# SCH_esp32s-Camper_2025-03-08.net
KiCad netlist of a schematic drawn in EasyEDA
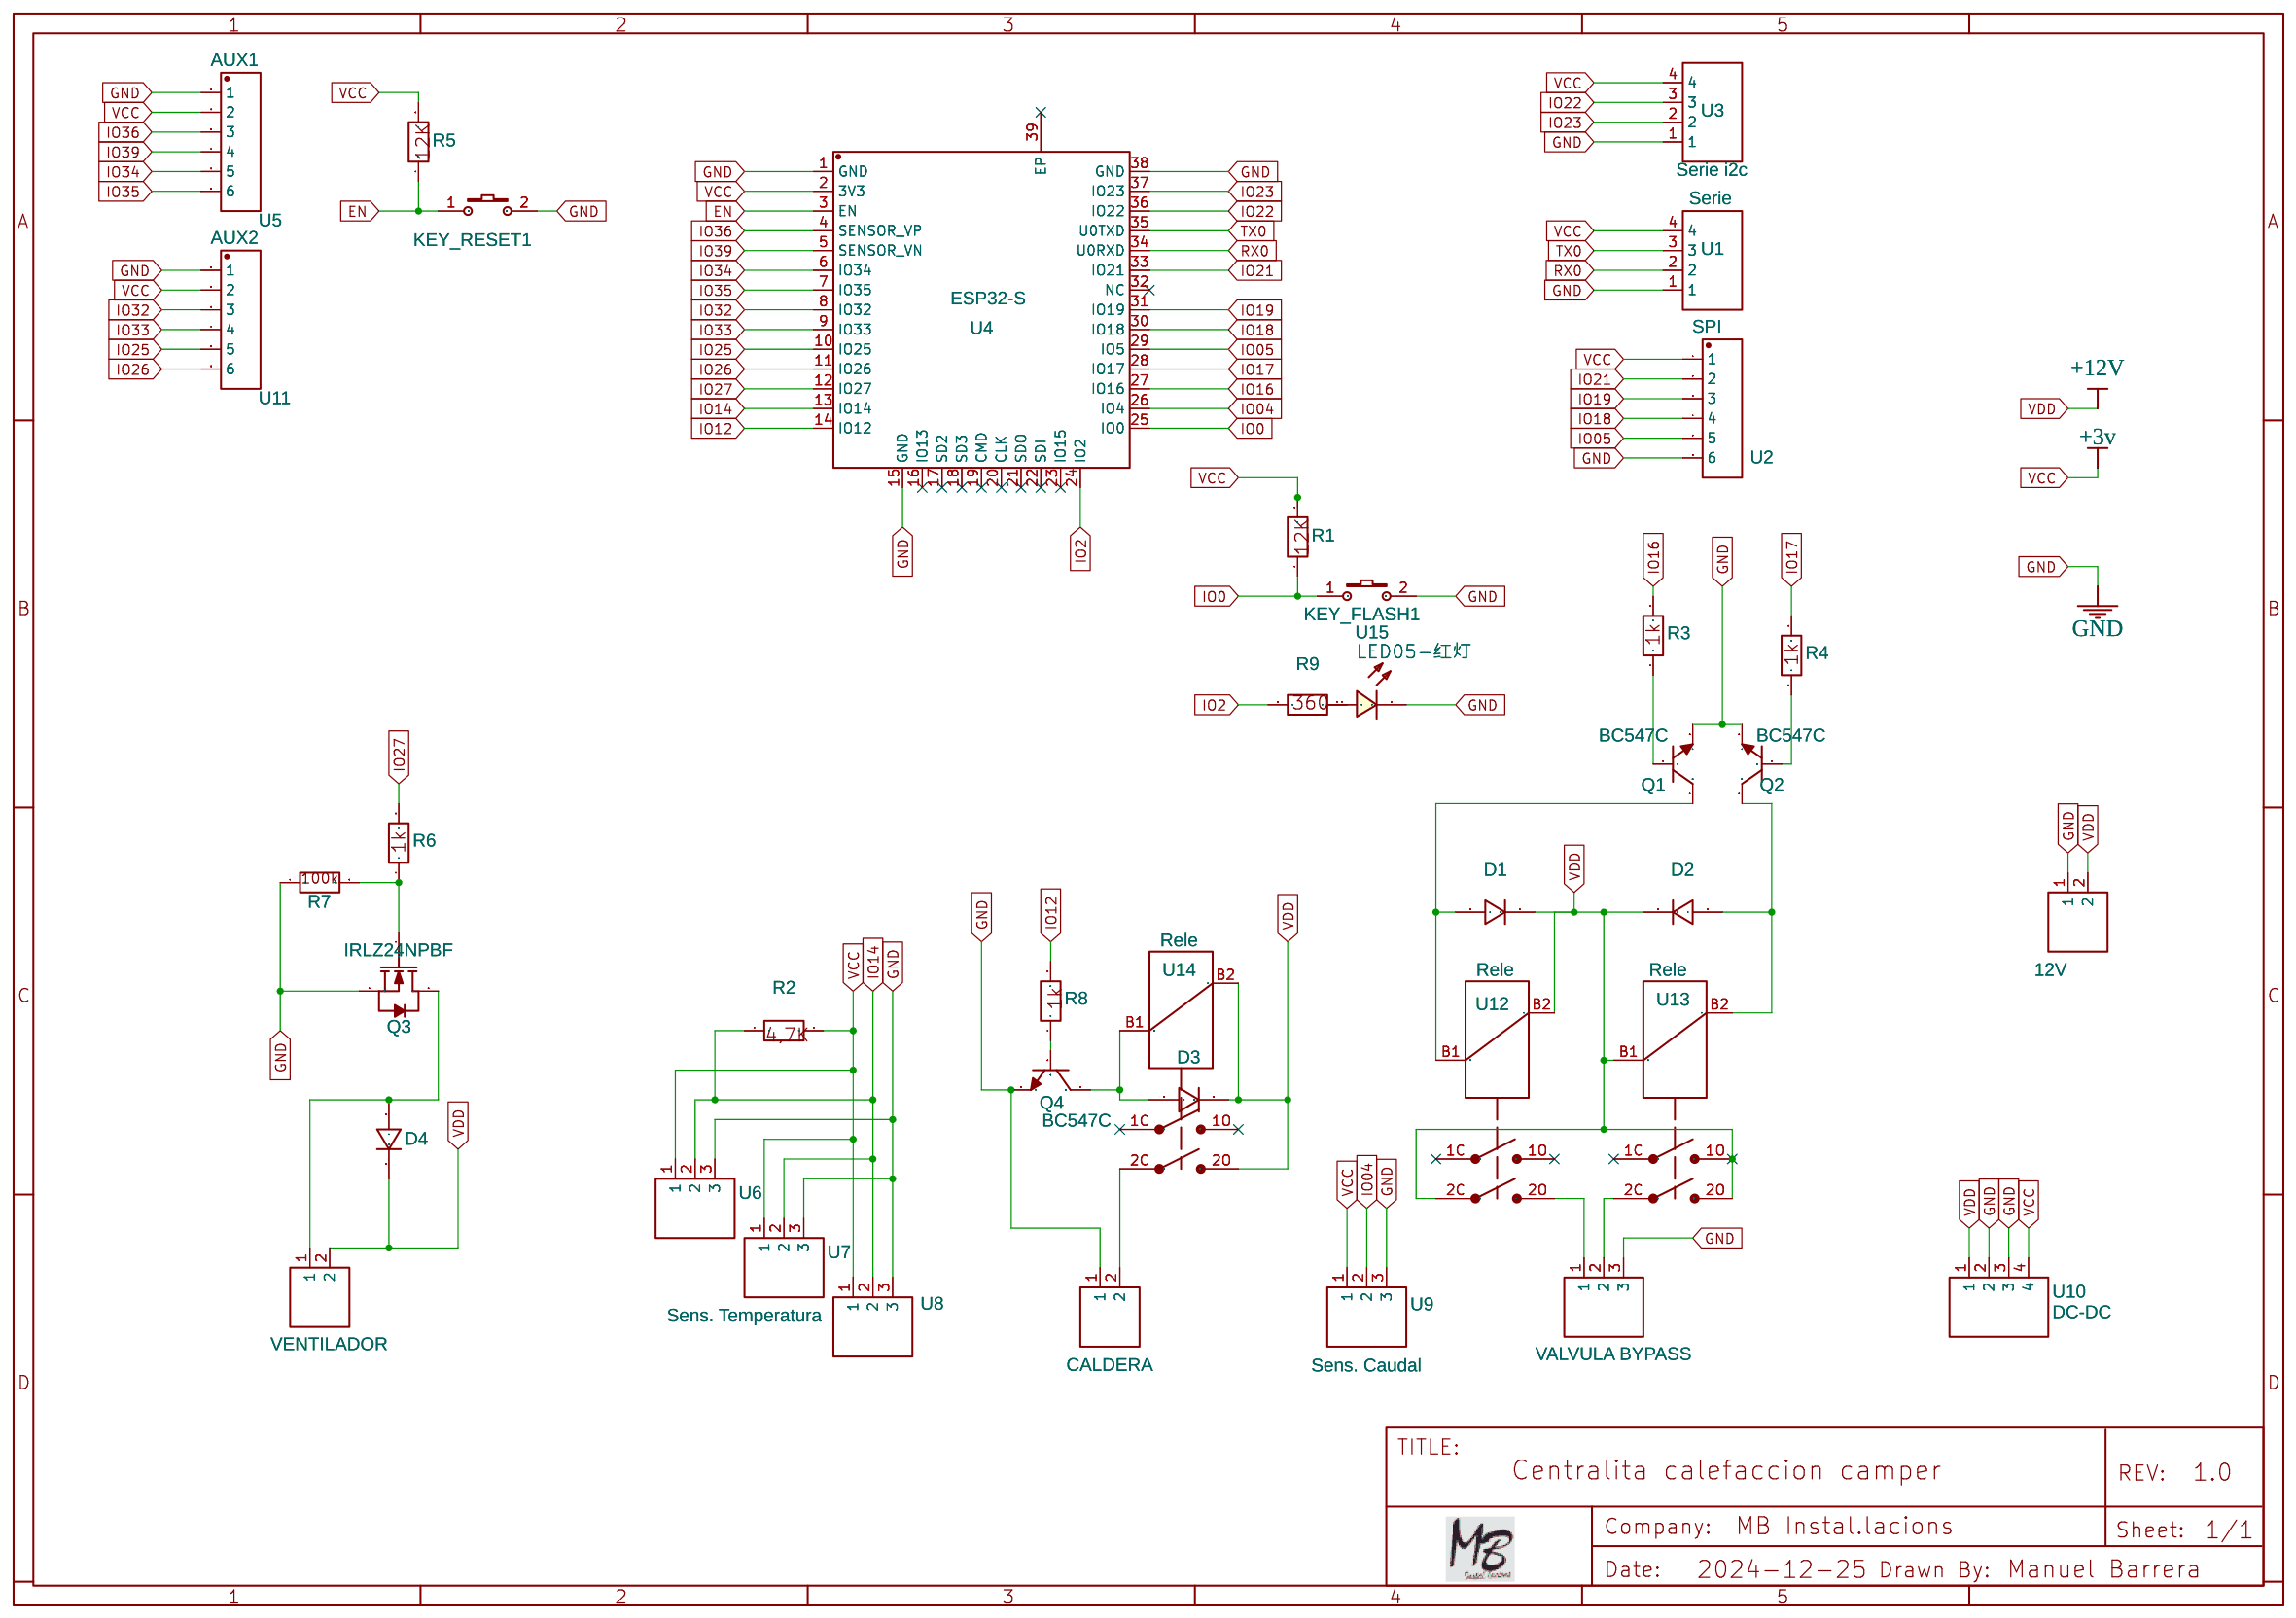
[diagram p0: schematic sheet]

(export (version "E")
  (design (tool "Eeschema 10.0.6"))
  (components
    (comp (ref "CALDERA1")
      (value "CALDERA")
      (fields (field (name "Manufacturer Part") "JST-XH02"))
      (libsource (lib "") (part "JST-XH02_1"))
    )
    (comp (ref "CALDERA2")
      (value "12V")
      (fields (field (name "Manufacturer Part") "JST-XH02"))
      (libsource (lib "") (part "JST-XH02_1"))
    )
    (comp (ref "D1")
      (value "1N4007-C115999")
      (fields (field (name "Manufacturer Part") "1N4007") (field (name "Manufacturer") "PANJIT"))
      (libsource (lib "") (part "1N4007-C115999_1"))
    )
    (comp (ref "D2")
      (value "1N4007-C115999")
      (fields (field (name "Manufacturer Part") "1N4007") (field (name "Manufacturer") "PANJIT"))
      (libsource (lib "") (part "1N4007-C115999"))
    )
    (comp (ref "D3")
      (value "1N4007-C115999")
      (fields (field (name "Manufacturer Part") "1N4007") (field (name "Manufacturer") "PANJIT"))
      (libsource (lib "") (part "1N4007-C115999_1"))
    )
    (comp (ref "D4")
      (value "1N4007-C115999")
      (fields (field (name "Manufacturer Part") "1N4007") (field (name "Manufacturer") "PANJIT"))
      (libsource (lib "") (part "1N4007-C115999_2"))
    )
    (comp (ref "KEY_FLASH1")
      (value "K2-3.6×6.1_SMD")
      (fields (field (name "Manufacturer Part") "K2-1107ST-A4SW-06"))
      (libsource (lib "") (part "K2-3.6×6.1_SMD"))
    )
    (comp (ref "KEY_RESET1")
      (value "K2-3.6×6.1_SMD")
      (fields (field (name "Manufacturer Part") "K2-1107ST-A4SW-06"))
      (libsource (lib "") (part "K2-3.6×6.1_SMD_1"))
    )
    (comp (ref "Q1")
      (value "BC547C")
      (fields (field (name "Manufacturer") "LGE"))
      (libsource (lib "") (part "BC547C_1"))
    )
    (comp (ref "Q2")
      (value "BC547C")
      (fields (field (name "Manufacturer") "LGE"))
      (libsource (lib "") (part "BC547C_2"))
    )
    (comp (ref "Q3")
      (value "IRLZ24NPBF")
      (fields (field (name "Manufacturer") "IR"))
      (libsource (lib "") (part "IRLZ24NPBF"))
    )
    (comp (ref "Q4")
      (value "BC547C")
      (fields (field (name "Manufacturer") "LGE"))
      (libsource (lib "") (part "BC547C"))
    )
    (comp (ref "R1") (value "RESISTENCIA_1/4") (libsource (lib "") (part "RESISTENCIA_1/4_2")))
    (comp (ref "R2") (value "RESISTENCIA_1/4") (libsource (lib "") (part "RESISTENCIA_1/4")))
    (comp (ref "R3") (value "RESISTENCIA_1/4") (libsource (lib "") (part "RESISTENCIA_1/4_1")))
    (comp (ref "R4") (value "RESISTENCIA_1/4") (libsource (lib "") (part "RESISTENCIA_1/4_1")))
    (comp (ref "R5") (value "RESISTENCIA_1/4") (libsource (lib "") (part "RESISTENCIA_1/4_2")))
    (comp (ref "R6") (value "RESISTENCIA_1/4") (libsource (lib "") (part "RESISTENCIA_1/4_1")))
    (comp (ref "R7") (value "RESISTENCIA_1/4") (libsource (lib "") (part "RESISTENCIA_1/4_5")))
    (comp (ref "R8") (value "RESISTENCIA_1/4") (libsource (lib "") (part "RESISTENCIA_1/4_4")))
    (comp (ref "R9") (value "RESISTENCIA_1/4") (libsource (lib "") (part "RESISTENCIA_1/4_3")))
    (comp (ref "U1")
      (value "Serie")
      (fields (field (name "Manufacturer Part") "JST-XH04"))
      (libsource (lib "") (part "JST-XH04"))
    )
    (comp (ref "U2")
      (value "SPI")
      (fields (field (name "Manufacturer Part") "06JQ-BT") (field (name "Manufacturer") "JST"))
      (libsource (lib "") (part "06JQ-BT COPY"))
    )
    (comp (ref "U3")
      (value "Serie i2c")
      (fields (field (name "Manufacturer Part") "JST-XH04"))
      (libsource (lib "") (part "JST-XH04"))
    )
    (comp (ref "U4")
      (value "ESP32-S")
      (fields (field (name "Manufacturer") "Ai-Thinker(安信可)"))
      (libsource (lib "") (part "ESP32-S"))
    )
    (comp (ref "U5")
      (value "AUX1")
      (fields (field (name "Manufacturer Part") "06JQ-BT") (field (name "Manufacturer") "JST"))
      (libsource (lib "") (part "06JQ-BT COPY"))
    )
    (comp (ref "U6")
      (value "Sens. Temperatura")
      (fields (field (name "Manufacturer Part") "JST-XH03"))
      (libsource (lib "") (part "JST-XH03_1"))
    )
    (comp (ref "U7")
      (value "Sens. Temperatura")
      (fields (field (name "Manufacturer Part") "JST-XH03"))
      (libsource (lib "") (part "JST-XH03_1"))
    )
    (comp (ref "U8")
      (value "Sens. Temperatura")
      (fields (field (name "Manufacturer Part") "JST-XH03"))
      (libsource (lib "") (part "JST-XH03_1"))
    )
    (comp (ref "U9")
      (value "Sens. Caudal")
      (fields (field (name "Manufacturer Part") "JST-XH03"))
      (libsource (lib "") (part "JST-XH03_1"))
    )
    (comp (ref "U10")
      (value "DC-DC")
      (fields (field (name "Manufacturer Part") "JST-XH04"))
      (libsource (lib "") (part "JST-XH04_1"))
    )
    (comp (ref "U11")
      (value "AUX2")
      (fields (field (name "Manufacturer Part") "06JQ-BT") (field (name "Manufacturer") "JST"))
      (libsource (lib "") (part "06JQ-BT COPY"))
    )
    (comp (ref "U12") (value "Rele") (libsource (lib "") (part "Relé_REED-RALUX-12V-2C")))
    (comp (ref "U13") (value "Rele") (libsource (lib "") (part "Relé_REED-RALUX-12V-2C")))
    (comp (ref "U14") (value "Rele") (libsource (lib "") (part "Relé_REED-RALUX-12V-2C")))
    (comp (ref "U15") (value "LED05-红灯") (libsource (lib "") (part "LED05-红灯")))
    (comp (ref "VALVULA1")
      (value "VALVULA BYPASS")
      (fields (field (name "Manufacturer Part") "JST-XH03"))
      (libsource (lib "") (part "JST-XH03"))
    )
    (comp (ref "VENTILADOR")
      (value "u9")
      (fields (field (name "Manufacturer Part") "JST-XH02"))
      (libsource (lib "") (part "JST-XH02"))
    )
  )
  (nets
    (net (code "1") (name "EN") (class "Default")
      (node (ref "KEY_RESET1") (pin "1") (pinfunction "1_1") (pintype "unspecified"))
      (node (ref "R5") (pin "1") (pinfunction "1_1") (pintype "unspecified"))
      (node (ref "U4") (pin "3") (pinfunction "EN_3") (pintype "unspecified"))
    )
    (net (code "2") (name "GND") (class "Default")
      (node (ref "CALDERA1") (pin "1") (pinfunction "1_1") (pintype "unspecified"))
      (node (ref "CALDERA2") (pin "1") (pinfunction "1_1") (pintype "unspecified"))
      (node (ref "KEY_FLASH1") (pin "2") (pinfunction "2_2") (pintype "unspecified"))
      (node (ref "KEY_RESET1") (pin "2") (pinfunction "2_2") (pintype "unspecified"))
      (node (ref "Q1") (pin "3") (pinfunction "E_3") (pintype "input"))
      (node (ref "Q2") (pin "3") (pinfunction "E_3") (pintype "input"))
      (node (ref "Q3") (pin "3") (pinfunction "S_3") (pintype "unspecified"))
      (node (ref "Q4") (pin "3") (pinfunction "E_3") (pintype "input"))
      (node (ref "R7") (pin "1") (pinfunction "1_1") (pintype "unspecified"))
      (node (ref "U1") (pin "1") (pinfunction "1_1") (pintype "unspecified"))
      (node (ref "U10") (pin "2") (pinfunction "2_2") (pintype "unspecified"))
      (node (ref "U10") (pin "3") (pinfunction "3_3") (pintype "unspecified"))
      (node (ref "U11") (pin "1") (pinfunction "1_1") (pintype "unspecified"))
      (node (ref "U15") (pin "2") (pinfunction "2_2") (pintype "unspecified"))
      (node (ref "U2") (pin "6") (pinfunction "6_6") (pintype "unspecified"))
      (node (ref "U3") (pin "1") (pinfunction "1_1") (pintype "unspecified"))
      (node (ref "U4") (pin "1") (pinfunction "GND_1") (pintype "unspecified"))
      (node (ref "U4") (pin "15") (pinfunction "GND_15") (pintype "unspecified"))
      (node (ref "U4") (pin "38") (pinfunction "GND_38") (pintype "unspecified"))
      (node (ref "U5") (pin "1") (pinfunction "1_1") (pintype "unspecified"))
      (node (ref "U6") (pin "3") (pinfunction "3_3") (pintype "unspecified"))
      (node (ref "U7") (pin "3") (pinfunction "3_3") (pintype "unspecified"))
      (node (ref "U8") (pin "3") (pinfunction "3_3") (pintype "unspecified"))
      (node (ref "U9") (pin "3") (pinfunction "3_3") (pintype "unspecified"))
      (node (ref "VALVULA1") (pin "3") (pinfunction "3_3") (pintype "unspecified"))
    )
    (net (code "3") (name "IO0") (class "Default")
      (node (ref "KEY_FLASH1") (pin "1") (pinfunction "1_1") (pintype "unspecified"))
      (node (ref "R1") (pin "1") (pinfunction "1_1") (pintype "unspecified"))
      (node (ref "U4") (pin "25") (pinfunction "IO0_25") (pintype "unspecified"))
    )
    (net (code "4") (name "IO2") (class "Default")
      (node (ref "R9") (pin "2") (pinfunction "2_2") (pintype "unspecified"))
      (node (ref "U4") (pin "24") (pinfunction "IO2_24") (pintype "unspecified"))
    )
    (net (code "5") (name "IO04") (class "Default")
      (node (ref "U4") (pin "26") (pinfunction "IO4_26") (pintype "unspecified"))
      (node (ref "U9") (pin "2") (pinfunction "2_2") (pintype "unspecified"))
    )
    (net (code "6") (name "IO05") (class "Default")
      (node (ref "U2") (pin "5") (pinfunction "5_5") (pintype "unspecified"))
      (node (ref "U4") (pin "29") (pinfunction "IO5_29") (pintype "unspecified"))
    )
    (net (code "7") (name "IO12") (class "Default")
      (node (ref "R8") (pin "2") (pinfunction "2_2") (pintype "unspecified"))
      (node (ref "U4") (pin "14") (pinfunction "IO12_14") (pintype "unspecified"))
    )
    (net (code "8") (name "IO14") (class "Default")
      (node (ref "R2") (pin "1") (pinfunction "1_1") (pintype "unspecified"))
      (node (ref "U4") (pin "13") (pinfunction "IO14_13") (pintype "unspecified"))
      (node (ref "U6") (pin "2") (pinfunction "2_2") (pintype "unspecified"))
      (node (ref "U7") (pin "2") (pinfunction "2_2") (pintype "unspecified"))
      (node (ref "U8") (pin "2") (pinfunction "2_2") (pintype "unspecified"))
    )
    (net (code "9") (name "IO16") (class "Default")
      (node (ref "R3") (pin "2") (pinfunction "2_2") (pintype "unspecified"))
      (node (ref "U4") (pin "27") (pinfunction "IO16_27") (pintype "unspecified"))
    )
    (net (code "10") (name "IO17") (class "Default")
      (node (ref "R4") (pin "2") (pinfunction "2_2") (pintype "unspecified"))
      (node (ref "U4") (pin "28") (pinfunction "IO17_28") (pintype "unspecified"))
    )
    (net (code "11") (name "IO18") (class "Default")
      (node (ref "U2") (pin "4") (pinfunction "4_4") (pintype "unspecified"))
      (node (ref "U4") (pin "30") (pinfunction "IO18_30") (pintype "unspecified"))
    )
    (net (code "12") (name "IO19") (class "Default")
      (node (ref "U2") (pin "3") (pinfunction "3_3") (pintype "unspecified"))
      (node (ref "U4") (pin "31") (pinfunction "IO19_31") (pintype "unspecified"))
    )
    (net (code "13") (name "IO21") (class "Default")
      (node (ref "U2") (pin "2") (pinfunction "2_2") (pintype "unspecified"))
      (node (ref "U4") (pin "33") (pinfunction "IO21_33") (pintype "unspecified"))
    )
    (net (code "14") (name "IO22") (class "Default")
      (node (ref "U3") (pin "3") (pinfunction "3_3") (pintype "unspecified"))
      (node (ref "U4") (pin "36") (pinfunction "IO22_36") (pintype "unspecified"))
    )
    (net (code "15") (name "IO23") (class "Default")
      (node (ref "U3") (pin "2") (pinfunction "2_2") (pintype "unspecified"))
      (node (ref "U4") (pin "37") (pinfunction "IO23_37") (pintype "unspecified"))
    )
    (net (code "16") (name "IO25") (class "Default")
      (node (ref "U11") (pin "5") (pinfunction "5_5") (pintype "unspecified"))
      (node (ref "U4") (pin "10") (pinfunction "IO25_10") (pintype "unspecified"))
    )
    (net (code "17") (name "IO26") (class "Default")
      (node (ref "U11") (pin "6") (pinfunction "6_6") (pintype "unspecified"))
      (node (ref "U4") (pin "11") (pinfunction "IO26_11") (pintype "unspecified"))
    )
    (net (code "18") (name "IO27") (class "Default")
      (node (ref "R6") (pin "2") (pinfunction "2_2") (pintype "unspecified"))
      (node (ref "U4") (pin "12") (pinfunction "IO27_12") (pintype "unspecified"))
    )
    (net (code "19") (name "IO32") (class "Default")
      (node (ref "U11") (pin "3") (pinfunction "3_3") (pintype "unspecified"))
      (node (ref "U4") (pin "8") (pinfunction "IO32_8") (pintype "unspecified"))
    )
    (net (code "20") (name "IO33") (class "Default")
      (node (ref "U11") (pin "4") (pinfunction "4_4") (pintype "unspecified"))
      (node (ref "U4") (pin "9") (pinfunction "IO33_9") (pintype "unspecified"))
    )
    (net (code "21") (name "IO34") (class "Default")
      (node (ref "U4") (pin "6") (pinfunction "IO34_6") (pintype "unspecified"))
      (node (ref "U5") (pin "5") (pinfunction "5_5") (pintype "unspecified"))
    )
    (net (code "22") (name "IO35") (class "Default")
      (node (ref "U4") (pin "7") (pinfunction "IO35_7") (pintype "unspecified"))
      (node (ref "U5") (pin "6") (pinfunction "6_6") (pintype "unspecified"))
    )
    (net (code "23") (name "IO36") (class "Default")
      (node (ref "U4") (pin "4") (pinfunction "SENSOR_VP_4") (pintype "unspecified"))
      (node (ref "U5") (pin "3") (pinfunction "3_3") (pintype "unspecified"))
    )
    (net (code "24") (name "IO39") (class "Default")
      (node (ref "U4") (pin "5") (pinfunction "SENSOR_VN_5") (pintype "unspecified"))
      (node (ref "U5") (pin "4") (pinfunction "4_4") (pintype "unspecified"))
    )
    (net (code "25") (name "Net-(CALDERA1-Pad2)") (class "Default")
      (node (ref "CALDERA1") (pin "2") (pinfunction "2_2") (pintype "unspecified"))
      (node (ref "U14") (pin "2C") (pinfunction "1_2C") (pintype "unspecified"))
    )
    (net (code "26") (name "Net-(D1-A)") (class "Default")
      (node (ref "D1") (pin "2") (pinfunction "A_2") (pintype "unspecified"))
      (node (ref "Q1") (pin "1") (pinfunction "C_1") (pintype "input"))
      (node (ref "U12") (pin "B1") (pinfunction "5_B1") (pintype "unspecified"))
    )
    (net (code "27") (name "Net-(D2-A)") (class "Default")
      (node (ref "D2") (pin "2") (pinfunction "A_2") (pintype "unspecified"))
      (node (ref "Q2") (pin "1") (pinfunction "C_1") (pintype "input"))
      (node (ref "U13") (pin "B2") (pinfunction "4_B2") (pintype "unspecified"))
    )
    (net (code "28") (name "Net-(D3-A)") (class "Default")
      (node (ref "D3") (pin "2") (pinfunction "A_2") (pintype "unspecified"))
      (node (ref "Q4") (pin "1") (pinfunction "C_1") (pintype "input"))
      (node (ref "U14") (pin "B1") (pinfunction "5_B1") (pintype "unspecified"))
    )
    (net (code "29") (name "Net-(D4-A)") (class "Default")
      (node (ref "D4") (pin "2") (pinfunction "A_2") (pintype "unspecified"))
      (node (ref "Q3") (pin "2") (pinfunction "D_2") (pintype "unspecified"))
      (node (ref "VENTILADOR") (pin "1") (pinfunction "1_1") (pintype "unspecified"))
    )
    (net (code "30") (name "Net-(Q1-B)") (class "Default")
      (node (ref "Q1") (pin "2") (pinfunction "B_2") (pintype "input"))
      (node (ref "R3") (pin "1") (pinfunction "1_1") (pintype "unspecified"))
    )
    (net (code "31") (name "Net-(Q2-B)") (class "Default")
      (node (ref "Q2") (pin "2") (pinfunction "B_2") (pintype "input"))
      (node (ref "R4") (pin "1") (pinfunction "1_1") (pintype "unspecified"))
    )
    (net (code "32") (name "Net-(Q3-G)") (class "Default")
      (node (ref "Q3") (pin "1") (pinfunction "G_1") (pintype "unspecified"))
      (node (ref "R6") (pin "1") (pinfunction "1_1") (pintype "unspecified"))
      (node (ref "R7") (pin "2") (pinfunction "2_2") (pintype "unspecified"))
    )
    (net (code "33") (name "Net-(Q4-B)") (class "Default")
      (node (ref "Q4") (pin "2") (pinfunction "B_2") (pintype "input"))
      (node (ref "R8") (pin "1") (pinfunction "1_1") (pintype "unspecified"))
    )
    (net (code "34") (name "Net-(R9-Pad1)") (class "Default")
      (node (ref "R9") (pin "1") (pinfunction "1_1") (pintype "unspecified"))
      (node (ref "U15") (pin "1") (pinfunction "1_1") (pintype "unspecified"))
    )
    (net (code "35") (name "Net-(U12-2-Pad2O)") (class "Default")
      (node (ref "U12") (pin "2O") (pinfunction "2_2O") (pintype "unspecified"))
      (node (ref "VALVULA1") (pin "1") (pinfunction "1_1") (pintype "unspecified"))
    )
    (net (code "36") (name "Net-(U13-1-Pad2C)") (class "Default")
      (node (ref "U13") (pin "2C") (pinfunction "1_2C") (pintype "unspecified"))
      (node (ref "VALVULA1") (pin "2") (pinfunction "2_2") (pintype "unspecified"))
    )
    (net (code "37") (name "RX0") (class "Default")
      (node (ref "U1") (pin "2") (pinfunction "2_2") (pintype "unspecified"))
      (node (ref "U4") (pin "34") (pinfunction "U0RXD_34") (pintype "unspecified"))
    )
    (net (code "38") (name "TX0") (class "Default")
      (node (ref "U1") (pin "3") (pinfunction "3_3") (pintype "unspecified"))
      (node (ref "U4") (pin "35") (pinfunction "U0TXD_35") (pintype "unspecified"))
    )
    (net (code "39") (name "VCC") (class "Default")
      (node (ref "R1") (pin "2") (pinfunction "2_2") (pintype "unspecified"))
      (node (ref "R2") (pin "2") (pinfunction "2_2") (pintype "unspecified"))
      (node (ref "R5") (pin "2") (pinfunction "2_2") (pintype "unspecified"))
      (node (ref "U1") (pin "4") (pinfunction "4_4") (pintype "unspecified"))
      (node (ref "U10") (pin "4") (pinfunction "4_4") (pintype "unspecified"))
      (node (ref "U11") (pin "2") (pinfunction "2_2") (pintype "unspecified"))
      (node (ref "U2") (pin "1") (pinfunction "1_1") (pintype "unspecified"))
      (node (ref "U3") (pin "4") (pinfunction "4_4") (pintype "unspecified"))
      (node (ref "U4") (pin "2") (pinfunction "3V3_2") (pintype "unspecified"))
      (node (ref "U5") (pin "2") (pinfunction "2_2") (pintype "unspecified"))
      (node (ref "U6") (pin "1") (pinfunction "1_1") (pintype "unspecified"))
      (node (ref "U7") (pin "1") (pinfunction "1_1") (pintype "unspecified"))
      (node (ref "U8") (pin "1") (pinfunction "1_1") (pintype "unspecified"))
      (node (ref "U9") (pin "1") (pinfunction "1_1") (pintype "unspecified"))
    )
    (net (code "40") (name "VDD") (class "Default")
      (node (ref "CALDERA2") (pin "2") (pinfunction "2_2") (pintype "unspecified"))
      (node (ref "D1") (pin "1") (pinfunction "C_1") (pintype "unspecified"))
      (node (ref "D2") (pin "1") (pinfunction "C_1") (pintype "unspecified"))
      (node (ref "D3") (pin "1") (pinfunction "C_1") (pintype "unspecified"))
      (node (ref "D4") (pin "1") (pinfunction "C_1") (pintype "unspecified"))
      (node (ref "U10") (pin "1") (pinfunction "1_1") (pintype "unspecified"))
      (node (ref "U12") (pin "2C") (pinfunction "1_2C") (pintype "unspecified"))
      (node (ref "U12") (pin "B2") (pinfunction "4_B2") (pintype "unspecified"))
      (node (ref "U13") (pin "1O") (pinfunction "2_1O") (pintype "unspecified"))
      (node (ref "U13") (pin "2O") (pinfunction "2_2O") (pintype "unspecified"))
      (node (ref "U13") (pin "B1") (pinfunction "5_B1") (pintype "unspecified"))
      (node (ref "U14") (pin "2O") (pinfunction "2_2O") (pintype "unspecified"))
      (node (ref "U14") (pin "B2") (pinfunction "4_B2") (pintype "unspecified"))
      (node (ref "VENTILADOR") (pin "2") (pinfunction "2_2") (pintype "unspecified"))
    )
    (net (code "41") (name "unconnected-(U4-CLK-Pad20)") (class "Default")
      (node (ref "U4") (pin "20") (pinfunction "CLK_20") (pintype "unspecified+no_connect"))
    )
    (net (code "42") (name "unconnected-(U4-CMD-Pad19)") (class "Default")
      (node (ref "U4") (pin "19") (pinfunction "CMD_19") (pintype "unspecified+no_connect"))
    )
    (net (code "43") (name "unconnected-(U4-EP-Pad39)") (class "Default")
      (node (ref "U4") (pin "39") (pinfunction "EP_39") (pintype "unspecified+no_connect"))
    )
    (net (code "44") (name "unconnected-(U4-IO13-Pad16)") (class "Default")
      (node (ref "U4") (pin "16") (pinfunction "IO13_16") (pintype "unspecified+no_connect"))
    )
    (net (code "45") (name "unconnected-(U4-IO15-Pad23)") (class "Default")
      (node (ref "U4") (pin "23") (pinfunction "IO15_23") (pintype "unspecified+no_connect"))
    )
    (net (code "46") (name "unconnected-(U4-NC-Pad32)") (class "Default")
      (node (ref "U4") (pin "32") (pinfunction "NC_32") (pintype "unspecified+no_connect"))
    )
    (net (code "47") (name "unconnected-(U4-SD2-Pad17)") (class "Default")
      (node (ref "U4") (pin "17") (pinfunction "SD2_17") (pintype "unspecified+no_connect"))
    )
    (net (code "48") (name "unconnected-(U4-SD3-Pad18)") (class "Default")
      (node (ref "U4") (pin "18") (pinfunction "SD3_18") (pintype "unspecified+no_connect"))
    )
    (net (code "49") (name "unconnected-(U4-SDI-Pad22)") (class "Default")
      (node (ref "U4") (pin "22") (pinfunction "SDI_22") (pintype "unspecified+no_connect"))
    )
    (net (code "50") (name "unconnected-(U4-SDO-Pad21)") (class "Default")
      (node (ref "U4") (pin "21") (pinfunction "SDO_21") (pintype "unspecified+no_connect"))
    )
    (net (code "51") (name "unconnected-(U12-1-Pad1C)") (class "Default")
      (node (ref "U12") (pin "1C") (pinfunction "1_1C") (pintype "unspecified+no_connect"))
    )
    (net (code "52") (name "unconnected-(U12-2-Pad1O)") (class "Default")
      (node (ref "U12") (pin "1O") (pinfunction "2_1O") (pintype "unspecified+no_connect"))
    )
    (net (code "53") (name "unconnected-(U13-1-Pad1C)") (class "Default")
      (node (ref "U13") (pin "1C") (pinfunction "1_1C") (pintype "unspecified+no_connect"))
    )
    (net (code "54") (name "unconnected-(U14-1-Pad1C)") (class "Default")
      (node (ref "U14") (pin "1C") (pinfunction "1_1C") (pintype "unspecified+no_connect"))
    )
    (net (code "55") (name "unconnected-(U14-2-Pad1O)") (class "Default")
      (node (ref "U14") (pin "1O") (pinfunction "2_1O") (pintype "unspecified+no_connect"))
    )
  )
)
